# Single_Mux.net
KiCad netlist of a schematic drawn in Altium Designer
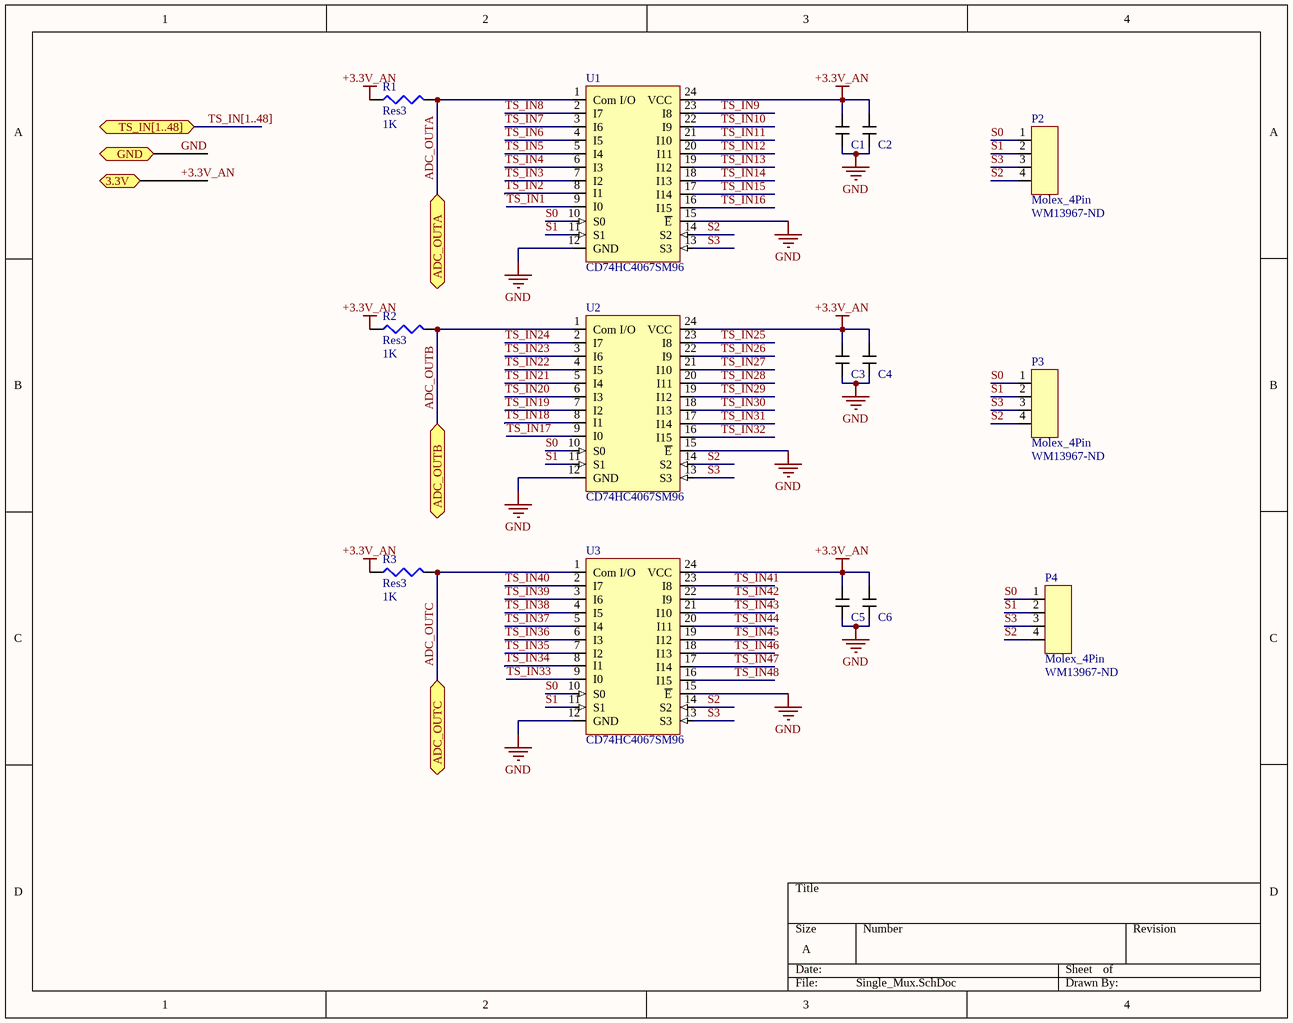
[diagram p0: Single_Mux.SchDoc]

(export (version "E")
  (design (tool "Eeschema 10.0.6"))
  (components
    (comp (ref "C1")
      (value "0.1uF Cap")
      (footprint "0.1uF_Kemet")
      (description "C0603C101K8GAC7867 Kemet Capacitor")
      (libsource (lib "0.1_uF_Kemet_Cap") (part "0.1uF Cap"))
    )
    (comp (ref "C2")
      (value "1uF Samsung Cap")
      (footprint "1uf_Samsung")
      (libsource (lib "1uF_Samsung_Cap") (part "1uF Samsung Cap"))
    )
    (comp (ref "C3")
      (value "0.1uF Cap")
      (footprint "0.1uF_Kemet")
      (description "C0603C101K8GAC7867 Kemet Capacitor")
      (libsource (lib "0.1_uF_Kemet_Cap") (part "0.1uF Cap"))
    )
    (comp (ref "C4")
      (value "1uF Samsung Cap")
      (footprint "1uf_Samsung")
      (libsource (lib "1uF_Samsung_Cap") (part "1uF Samsung Cap"))
    )
    (comp (ref "C5")
      (value "0.1uF Cap")
      (footprint "0.1uF_Kemet")
      (description "C0603C101K8GAC7867 Kemet Capacitor")
      (libsource (lib "0.1_uF_Kemet_Cap") (part "0.1uF Cap"))
    )
    (comp (ref "C6")
      (value "1uF Samsung Cap")
      (footprint "1uf_Samsung")
      (libsource (lib "1uF_Samsung_Cap") (part "1uF Samsung Cap"))
    )
    (comp (ref "P2")
      (value "Molex_4Pin")
      (footprint "MUX_SEL_CON")
      (fields (field (name "SUPPLIER PART NUMBER 1") "WM13967-ND"))
      (libsource (lib "4_Pin_Molex_Connector") (part "Component_1"))
    )
    (comp (ref "P3")
      (value "Molex_4Pin")
      (footprint "MUX_SEL_CON")
      (fields (field (name "SUPPLIER PART NUMBER 1") "WM13967-ND"))
      (libsource (lib "4_Pin_Molex_Connector") (part "Component_1"))
    )
    (comp (ref "P4")
      (value "Molex_4Pin")
      (footprint "MUX_SEL_CON")
      (fields (field (name "SUPPLIER PART NUMBER 1") "WM13967-ND"))
      (libsource (lib "4_Pin_Molex_Connector") (part "Component_1"))
    )
    (comp (ref "R1")
      (value "Res3")
      (footprint "J1-0603")
      (description "Resistor")
      (fields (field (name "ALTIUM_VALUE") "1K") (field (name "PUBLISHER") "Altium Limited"))
      (libsource (lib "Miscellaneous Devices") (part "Res3"))
    )
    (comp (ref "R2")
      (value "Res3")
      (footprint "J1-0603")
      (description "Resistor")
      (fields (field (name "ALTIUM_VALUE") "1K") (field (name "PUBLISHER") "Altium Limited"))
      (libsource (lib "Miscellaneous Devices") (part "Res3"))
    )
    (comp (ref "R3")
      (value "Res3")
      (footprint "J1-0603")
      (description "Resistor")
      (fields (field (name "ALTIUM_VALUE") "1K") (field (name "PUBLISHER") "Altium Limited"))
      (libsource (lib "Miscellaneous Devices") (part "Res3"))
    )
    (comp (ref "U1")
      (value "CD74HC4067SM96")
      (footprint "SOIC-24_MUX")
      (libsource (lib "TI_Mux") (part "CD74HC4067SM96"))
    )
    (comp (ref "U2")
      (value "CD74HC4067SM96")
      (footprint "SOIC-24_MUX")
      (libsource (lib "TI_Mux") (part "CD74HC4067SM96"))
    )
    (comp (ref "U3")
      (value "CD74HC4067SM96")
      (footprint "SOIC-24_MUX")
      (libsource (lib "TI_Mux") (part "CD74HC4067SM96"))
    )
  )
  (nets
    (net (code "1") (name "+3.3V_AN") (class "Default")
      (node (ref "C1") (pin "2") (pinfunction "2_2") (pintype "passive"))
      (node (ref "C2") (pin "2") (pinfunction "2_2") (pintype "passive"))
      (node (ref "C3") (pin "2") (pinfunction "2_2") (pintype "passive"))
      (node (ref "C4") (pin "2") (pinfunction "2_2") (pintype "passive"))
      (node (ref "C5") (pin "2") (pinfunction "2_2") (pintype "passive"))
      (node (ref "C6") (pin "2") (pinfunction "2_2") (pintype "passive"))
      (node (ref "R1") (pin "1") (pinfunction "1_1") (pintype "passive"))
      (node (ref "R2") (pin "1") (pinfunction "1_1") (pintype "passive"))
      (node (ref "R3") (pin "1") (pinfunction "1_1") (pintype "passive"))
      (node (ref "U1") (pin "24") (pinfunction "VCC_24") (pintype "passive"))
      (node (ref "U2") (pin "24") (pinfunction "VCC_24") (pintype "passive"))
      (node (ref "U3") (pin "24") (pinfunction "VCC_24") (pintype "passive"))
    )
    (net (code "2") (name "/ADC_OUTA") (class "Default")
      (node (ref "R1") (pin "2") (pinfunction "2_2") (pintype "passive"))
      (node (ref "U1") (pin "1") (pinfunction "Com_I/O_1") (pintype "passive"))
    )
    (net (code "3") (name "/ADC_OUTB") (class "Default")
      (node (ref "R2") (pin "2") (pinfunction "2_2") (pintype "passive"))
      (node (ref "U2") (pin "1") (pinfunction "Com_I/O_1") (pintype "passive"))
    )
    (net (code "4") (name "/ADC_OUTC") (class "Default")
      (node (ref "R3") (pin "2") (pinfunction "2_2") (pintype "passive"))
      (node (ref "U3") (pin "1") (pinfunction "Com_I/O_1") (pintype "passive"))
    )
    (net (code "5") (name "/S0") (class "Default")
      (node (ref "P2") (pin "1") (pintype "passive"))
      (node (ref "P3") (pin "1") (pintype "passive"))
      (node (ref "P4") (pin "1") (pintype "passive"))
      (node (ref "U1") (pin "10") (pinfunction "S0_10") (pintype "input"))
      (node (ref "U2") (pin "10") (pinfunction "S0_10") (pintype "input"))
      (node (ref "U3") (pin "10") (pinfunction "S0_10") (pintype "input"))
    )
    (net (code "6") (name "/S1") (class "Default")
      (node (ref "P2") (pin "2") (pintype "passive"))
      (node (ref "P3") (pin "2") (pintype "passive"))
      (node (ref "P4") (pin "2") (pintype "passive"))
      (node (ref "U1") (pin "11") (pinfunction "S1_11") (pintype "input"))
      (node (ref "U2") (pin "11") (pinfunction "S1_11") (pintype "input"))
      (node (ref "U3") (pin "11") (pinfunction "S1_11") (pintype "input"))
    )
    (net (code "7") (name "/S2") (class "Default")
      (node (ref "P2") (pin "4") (pintype "passive"))
      (node (ref "P3") (pin "4") (pintype "passive"))
      (node (ref "P4") (pin "4") (pintype "passive"))
      (node (ref "U1") (pin "14") (pinfunction "S2_14") (pintype "input"))
      (node (ref "U2") (pin "14") (pinfunction "S2_14") (pintype "input"))
      (node (ref "U3") (pin "14") (pinfunction "S2_14") (pintype "input"))
    )
    (net (code "8") (name "/S3") (class "Default")
      (node (ref "P2") (pin "3") (pintype "passive"))
      (node (ref "P3") (pin "3") (pintype "passive"))
      (node (ref "P4") (pin "3") (pintype "passive"))
      (node (ref "U1") (pin "13") (pinfunction "S3_13") (pintype "input"))
      (node (ref "U2") (pin "13") (pinfunction "S3_13") (pintype "input"))
      (node (ref "U3") (pin "13") (pinfunction "S3_13") (pintype "input"))
    )
    (net (code "9") (name "/TS_IN1") (class "Default")
      (node (ref "U1") (pin "9") (pinfunction "I0_9") (pintype "passive"))
    )
    (net (code "10") (name "/TS_IN2") (class "Default")
      (node (ref "U1") (pin "8") (pinfunction "I1_8") (pintype "passive"))
    )
    (net (code "11") (name "/TS_IN3") (class "Default")
      (node (ref "U1") (pin "7") (pinfunction "I2_7") (pintype "passive"))
    )
    (net (code "12") (name "/TS_IN4") (class "Default")
      (node (ref "U1") (pin "6") (pinfunction "I3_6") (pintype "passive"))
    )
    (net (code "13") (name "/TS_IN5") (class "Default")
      (node (ref "U1") (pin "5") (pinfunction "I4_5") (pintype "passive"))
    )
    (net (code "14") (name "/TS_IN6") (class "Default")
      (node (ref "U1") (pin "4") (pinfunction "I5_4") (pintype "passive"))
    )
    (net (code "15") (name "/TS_IN7") (class "Default")
      (node (ref "U1") (pin "3") (pinfunction "I6_3") (pintype "passive"))
    )
    (net (code "16") (name "/TS_IN8") (class "Default")
      (node (ref "U1") (pin "2") (pinfunction "I7_2") (pintype "passive"))
    )
    (net (code "17") (name "/TS_IN9") (class "Default")
      (node (ref "U1") (pin "23") (pinfunction "I8_23") (pintype "passive"))
    )
    (net (code "18") (name "/TS_IN10") (class "Default")
      (node (ref "U1") (pin "22") (pinfunction "I9_22") (pintype "passive"))
    )
    (net (code "19") (name "/TS_IN11") (class "Default")
      (node (ref "U1") (pin "21") (pinfunction "I10_21") (pintype "passive"))
    )
    (net (code "20") (name "/TS_IN12") (class "Default")
      (node (ref "U1") (pin "20") (pinfunction "I11_20") (pintype "passive"))
    )
    (net (code "21") (name "/TS_IN13") (class "Default")
      (node (ref "U1") (pin "19") (pinfunction "I12_19") (pintype "passive"))
    )
    (net (code "22") (name "/TS_IN14") (class "Default")
      (node (ref "U1") (pin "18") (pinfunction "I13_18") (pintype "passive"))
    )
    (net (code "23") (name "/TS_IN15") (class "Default")
      (node (ref "U1") (pin "17") (pinfunction "I14_17") (pintype "passive"))
    )
    (net (code "24") (name "/TS_IN16") (class "Default")
      (node (ref "U1") (pin "16") (pinfunction "I15_16") (pintype "passive"))
    )
    (net (code "25") (name "/TS_IN17") (class "Default")
      (node (ref "U2") (pin "9") (pinfunction "I0_9") (pintype "passive"))
    )
    (net (code "26") (name "/TS_IN18") (class "Default")
      (node (ref "U2") (pin "8") (pinfunction "I1_8") (pintype "passive"))
    )
    (net (code "27") (name "/TS_IN19") (class "Default")
      (node (ref "U2") (pin "7") (pinfunction "I2_7") (pintype "passive"))
    )
    (net (code "28") (name "/TS_IN20") (class "Default")
      (node (ref "U2") (pin "6") (pinfunction "I3_6") (pintype "passive"))
    )
    (net (code "29") (name "/TS_IN21") (class "Default")
      (node (ref "U2") (pin "5") (pinfunction "I4_5") (pintype "passive"))
    )
    (net (code "30") (name "/TS_IN22") (class "Default")
      (node (ref "U2") (pin "4") (pinfunction "I5_4") (pintype "passive"))
    )
    (net (code "31") (name "/TS_IN23") (class "Default")
      (node (ref "U2") (pin "3") (pinfunction "I6_3") (pintype "passive"))
    )
    (net (code "32") (name "/TS_IN24") (class "Default")
      (node (ref "U2") (pin "2") (pinfunction "I7_2") (pintype "passive"))
    )
    (net (code "33") (name "/TS_IN25") (class "Default")
      (node (ref "U2") (pin "23") (pinfunction "I8_23") (pintype "passive"))
    )
    (net (code "34") (name "/TS_IN26") (class "Default")
      (node (ref "U2") (pin "22") (pinfunction "I9_22") (pintype "passive"))
    )
    (net (code "35") (name "/TS_IN27") (class "Default")
      (node (ref "U2") (pin "21") (pinfunction "I10_21") (pintype "passive"))
    )
    (net (code "36") (name "/TS_IN28") (class "Default")
      (node (ref "U2") (pin "20") (pinfunction "I11_20") (pintype "passive"))
    )
    (net (code "37") (name "/TS_IN29") (class "Default")
      (node (ref "U2") (pin "19") (pinfunction "I12_19") (pintype "passive"))
    )
    (net (code "38") (name "/TS_IN30") (class "Default")
      (node (ref "U2") (pin "18") (pinfunction "I13_18") (pintype "passive"))
    )
    (net (code "39") (name "/TS_IN31") (class "Default")
      (node (ref "U2") (pin "17") (pinfunction "I14_17") (pintype "passive"))
    )
    (net (code "40") (name "/TS_IN32") (class "Default")
      (node (ref "U2") (pin "16") (pinfunction "I15_16") (pintype "passive"))
    )
    (net (code "41") (name "/TS_IN33") (class "Default")
      (node (ref "U3") (pin "9") (pinfunction "I0_9") (pintype "passive"))
    )
    (net (code "42") (name "/TS_IN34") (class "Default")
      (node (ref "U3") (pin "8") (pinfunction "I1_8") (pintype "passive"))
    )
    (net (code "43") (name "/TS_IN35") (class "Default")
      (node (ref "U3") (pin "7") (pinfunction "I2_7") (pintype "passive"))
    )
    (net (code "44") (name "/TS_IN36") (class "Default")
      (node (ref "U3") (pin "6") (pinfunction "I3_6") (pintype "passive"))
    )
    (net (code "45") (name "/TS_IN37") (class "Default")
      (node (ref "U3") (pin "5") (pinfunction "I4_5") (pintype "passive"))
    )
    (net (code "46") (name "/TS_IN38") (class "Default")
      (node (ref "U3") (pin "4") (pinfunction "I5_4") (pintype "passive"))
    )
    (net (code "47") (name "/TS_IN39") (class "Default")
      (node (ref "U3") (pin "3") (pinfunction "I6_3") (pintype "passive"))
    )
    (net (code "48") (name "/TS_IN40") (class "Default")
      (node (ref "U3") (pin "2") (pinfunction "I7_2") (pintype "passive"))
    )
    (net (code "49") (name "/TS_IN41") (class "Default")
      (node (ref "U3") (pin "23") (pinfunction "I8_23") (pintype "passive"))
    )
    (net (code "50") (name "/TS_IN42") (class "Default")
      (node (ref "U3") (pin "22") (pinfunction "I9_22") (pintype "passive"))
    )
    (net (code "51") (name "/TS_IN43") (class "Default")
      (node (ref "U3") (pin "21") (pinfunction "I10_21") (pintype "passive"))
    )
    (net (code "52") (name "/TS_IN44") (class "Default")
      (node (ref "U3") (pin "20") (pinfunction "I11_20") (pintype "passive"))
    )
    (net (code "53") (name "/TS_IN45") (class "Default")
      (node (ref "U3") (pin "19") (pinfunction "I12_19") (pintype "passive"))
    )
    (net (code "54") (name "/TS_IN46") (class "Default")
      (node (ref "U3") (pin "18") (pinfunction "I13_18") (pintype "passive"))
    )
    (net (code "55") (name "/TS_IN47") (class "Default")
      (node (ref "U3") (pin "17") (pinfunction "I14_17") (pintype "passive"))
    )
    (net (code "56") (name "/TS_IN48") (class "Default")
      (node (ref "U3") (pin "16") (pinfunction "I15_16") (pintype "passive"))
    )
    (net (code "58") (name "GND") (class "Default")
      (node (ref "C1") (pin "1") (pinfunction "1_1") (pintype "passive"))
      (node (ref "C2") (pin "1") (pinfunction "1_1") (pintype "passive"))
      (node (ref "C3") (pin "1") (pinfunction "1_1") (pintype "passive"))
      (node (ref "C4") (pin "1") (pinfunction "1_1") (pintype "passive"))
      (node (ref "C5") (pin "1") (pinfunction "1_1") (pintype "passive"))
      (node (ref "C6") (pin "1") (pinfunction "1_1") (pintype "passive"))
      (node (ref "U1") (pin "12") (pinfunction "GND_12") (pintype "passive"))
      (node (ref "U1") (pin "15") (pinfunction "~{E}_15") (pintype "passive"))
      (node (ref "U2") (pin "12") (pinfunction "GND_12") (pintype "passive"))
      (node (ref "U2") (pin "15") (pinfunction "~{E}_15") (pintype "passive"))
      (node (ref "U3") (pin "12") (pinfunction "GND_12") (pintype "passive"))
      (node (ref "U3") (pin "15") (pinfunction "~{E}_15") (pintype "passive"))
    )
  )
)
